# 3V3_LDO_Regulator.net
KiCad netlist of a schematic drawn in Altium Designer
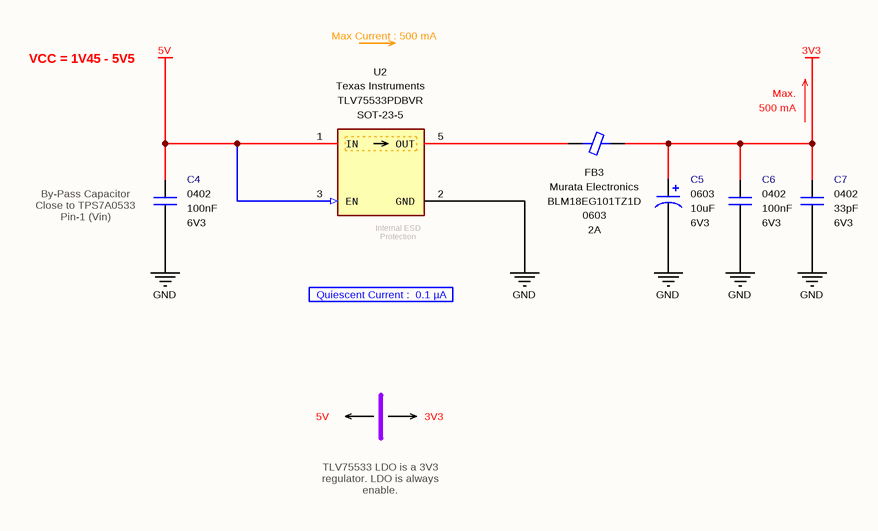
[diagram p0: 3V3 LDO Regulator.SchDoc]

(export (version "E")
  (design (tool "Eeschema 10.0.6"))
  (components
    (comp (ref "C4")
      (value "100nF")
      (footprint "CAPACITOR_0402")
      (description "Capacitor - 100nF [0402-6V3] (Ceramic)")
      (fields
        (field (name "CASE") "0402")
        (field (name "TOLERANCE") "%10")
        (field (name "VOLTAGE") "6V3")
        (field (name "MANUFACTURER PART NUMBER") "04026D104KAT4A")
      )
      (libsource (lib "Ovoo_Library") (part "Capacitor - 100nF [0402-6V3]"))
    )
    (comp (ref "C5")
      (value "10uF")
      (footprint "CAPACITOR_0603 - TANTALUM")
      (description "Capacitor - 10uF [0603] (Tantalium)")
      (fields
        (field (name "TOLERANCE") "20%")
        (field (name "CASE") "0603")
        (field (name "VOLTAGE") "6V3")
        (field (name "MANUFACTURER PART NUMBER") "F380J106MMAAH3")
      )
      (libsource (lib "Ovoo_Library") (part "Capacitor - 10uF [0603-6V3] (Tantalium)"))
    )
    (comp (ref "C6")
      (value "100nF")
      (footprint "CAPACITOR_0402")
      (description "Capacitor - 100nF [0402-6V3] (Ceramic)")
      (fields
        (field (name "TOLERANCE") "%10")
        (field (name "CASE") "0402")
        (field (name "VOLTAGE") "6V3")
        (field (name "MANUFACTURER PART NUMBER") "04026D104KAT4A")
      )
      (libsource (lib "Ovoo_Library") (part "Capacitor - 100nF [0402-6V3]"))
    )
    (comp (ref "C7")
      (value "33pF")
      (footprint "CAPACITOR_0402")
      (description "Capacitor - 33pF [0402] (Ceramic)")
      (fields
        (field (name "TOLERANCE") "10%")
        (field (name "CASE") "0402")
        (field (name "VOLTAGE") "6V3")
        (field (name "MANUFACTURER PART NUMBER") "C0402C330J9RACAUTO")
      )
      (libsource (lib "Ovoo_Library") (part "Capacitor - 33pF [0402-6V3]"))
    )
    (comp (ref "FB3")
      (value "BLM18EG101TZ1D")
      (footprint "INDUCATOR_0603")
      (description "Ferrite Beads 0603 100ohms 2000mA Auto Infotainment")
      (fields
        (field (name "TOLERANCE") "25%")
        (field (name "CASE") "0603")
        (field (name "MAXIMUM DC CURRENT") "2A")
        (field (name "MOUSER PART NUMBER") "81-BLM18EG101TZ1D")
        (field (name "MANUFACTURER NAME") "Murata Electronics")
      )
      (libsource (lib "Ovoo_Library") (part "Ferrite Bead - 2A [0603]"))
    )
    (comp (ref "U2")
      (value "LDO Voltage Regulator")
      (footprint "SOT-23-5")
      (description "LDO Voltage Regulators 500-mA low-IQ small-size low-dropout (LDO) regulator.")
      (fields
        (field (name "CASE") "SOT-23-5")
        (field (name "MOUSER PART NUMBER") "595-TLV75533PDBVR")
        (field (name "MANUFACTURER PART NUMBER") "TLV75533PDBVR")
        (field (name "MANUFACTURER NAME") "Texas Instruments")
      )
      (libsource (lib "Ovoo_Library") (part "IC - TLV75533PDBVR"))
    )
  )
  (nets
    (net (code "1") (name "3V3") (class "Default")
      (node (ref "C5") (pin "1") (pinfunction "1_1") (pintype "passive"))
      (node (ref "C6") (pin "2") (pinfunction "2_2") (pintype "passive"))
      (node (ref "C7") (pin "1") (pinfunction "1_1") (pintype "passive"))
      (node (ref "FB3") (pin "2") (pinfunction "2_2") (pintype "passive"))
    )
    (net (code "2") (name "5V") (class "Default")
      (node (ref "C4") (pin "1") (pinfunction "1_1") (pintype "passive"))
      (node (ref "U2") (pin "1") (pinfunction "IN_1") (pintype "power_in"))
      (node (ref "U2") (pin "3") (pinfunction "EN_3") (pintype "input"))
    )
    (net (code "3") (name "GND") (class "Default")
      (node (ref "C4") (pin "2") (pinfunction "2_2") (pintype "passive"))
      (node (ref "C5") (pin "2") (pinfunction "2_2") (pintype "passive"))
      (node (ref "C6") (pin "1") (pinfunction "1_1") (pintype "passive"))
      (node (ref "C7") (pin "2") (pinfunction "2_2") (pintype "passive"))
      (node (ref "U2") (pin "2") (pinfunction "GND_2") (pintype "passive"))
    )
    (net (code "4") (name "Net-(U2-OUT)") (class "Default")
      (node (ref "FB3") (pin "1") (pinfunction "1_1") (pintype "passive"))
      (node (ref "U2") (pin "5") (pinfunction "OUT_5") (pintype "power_in"))
    )
    (net (code "5") (name "unconnected-(U2-NC-Pad4)") (class "Default")
      (node (ref "U2") (pin "4") (pinfunction "NC_4") (pintype "passive"))
    )
  )
)
